# AK9753_Human_Movement_Sensor.net
KiCad netlist of a schematic drawn in EAGLE
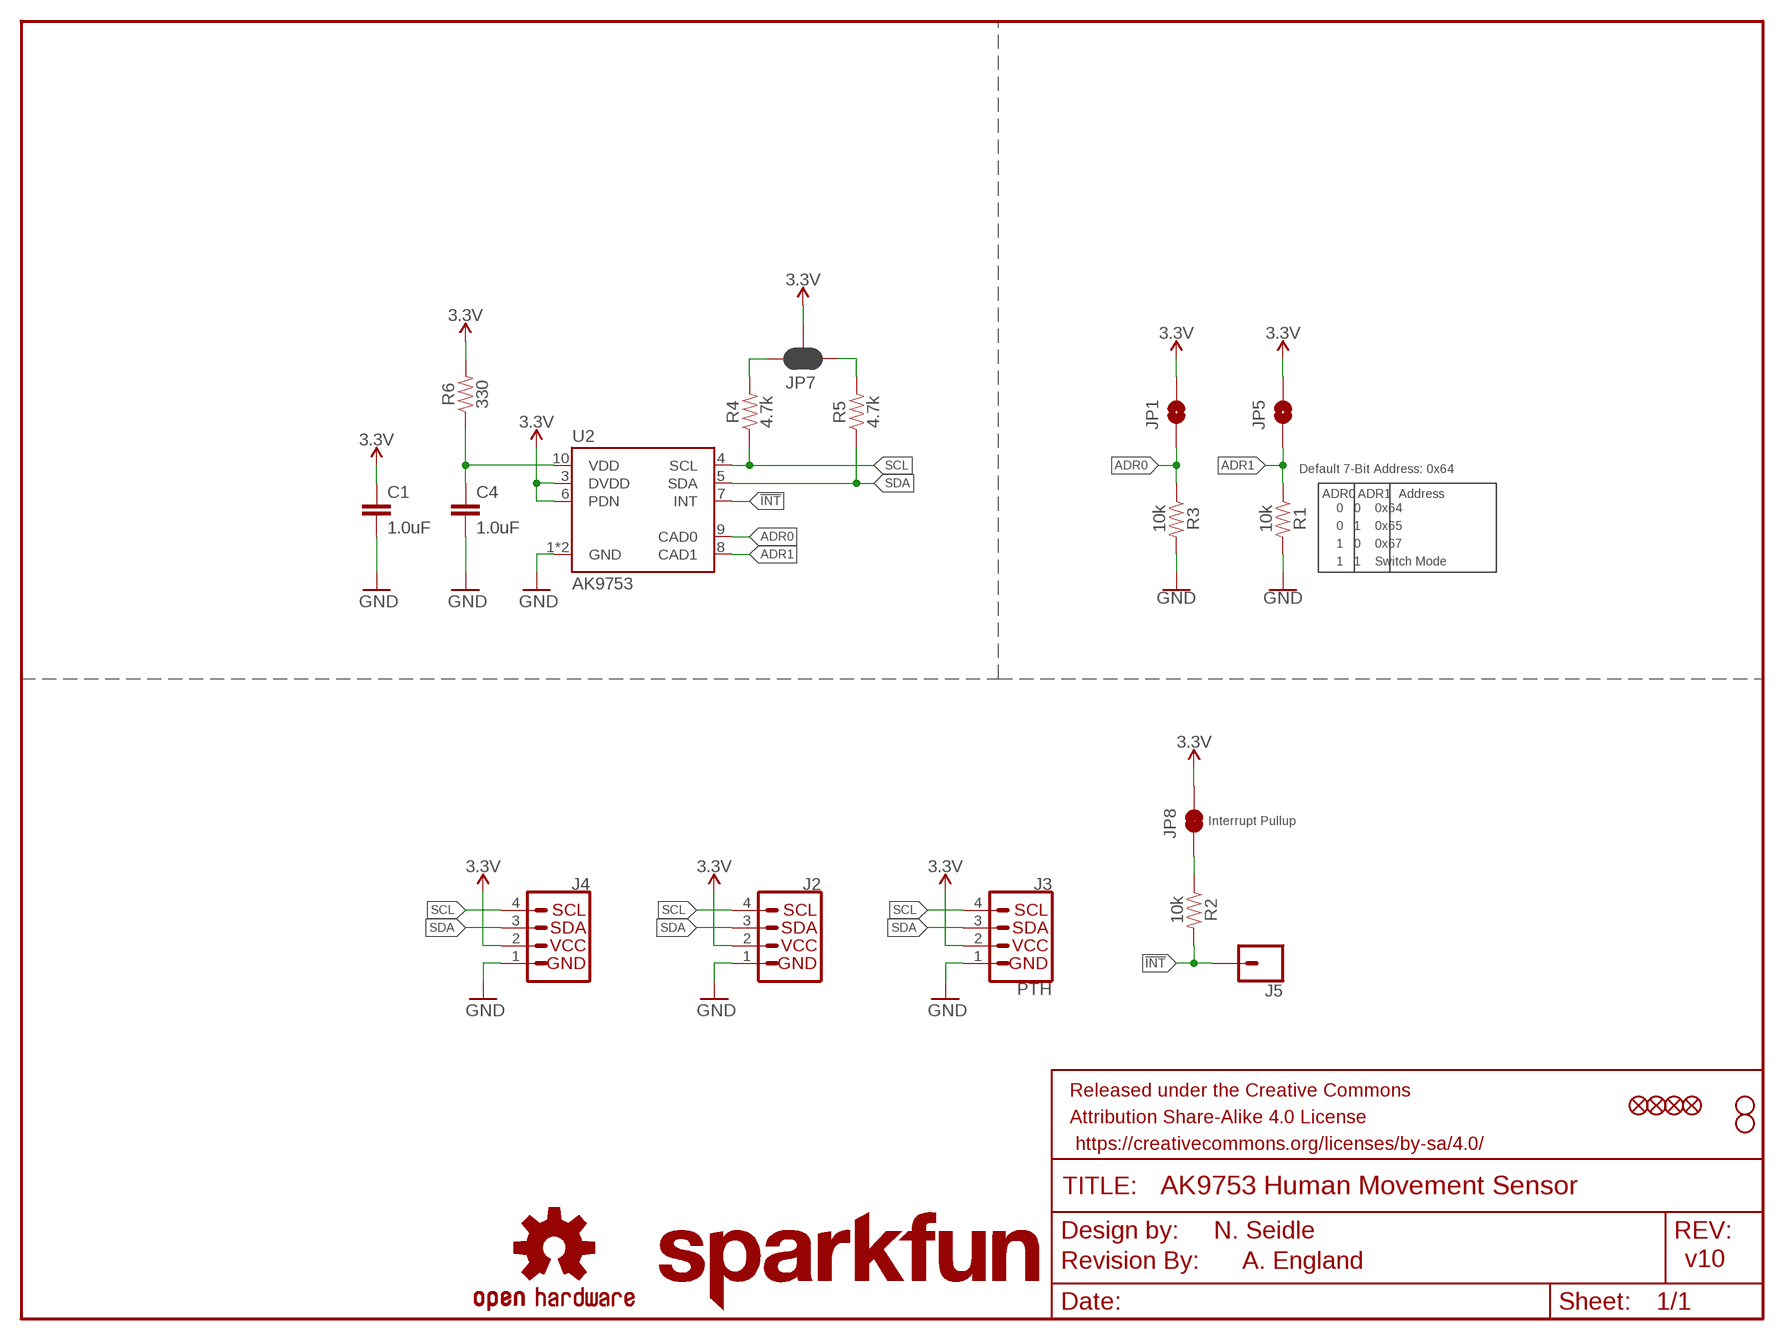
[diagram p0: schematic, sheet 1]

(export (version "E")
  (design (tool "Eeschema 10.0.6"))
  (components
    (comp (ref "C1")
      (value "1.0uF")
      (footprint "eagle-import:0603")
      (libsource (lib "eagle-import") (part "1.0UF-0603-16V-10%"))
    )
    (comp (ref "C4")
      (value "1.0uF")
      (footprint "eagle-import:0603")
      (libsource (lib "eagle-import") (part "1.0UF-0603-16V-10%"))
    )
    (comp (ref "FRAME1")
      (value "FRAME-LETTER")
      (footprint "eagle-import:CREATIVE_COMMONS")
      (libsource (lib "eagle-import") (part "FRAME-LETTER"))
    )
    (comp (ref "J2")
      (value "QWIIC_CONNECTORJS-1MM")
      (footprint "eagle-import:1X04_1MM_RA")
      (libsource (lib "eagle-import") (part "QWIIC_CONNECTORJS-1MM"))
    )
    (comp (ref "J3")
      (value "PTH")
      (footprint "eagle-import:1X04_NO_SILK")
      (libsource (lib "eagle-import") (part "I2C_STANDARD_NO_SILK"))
    )
    (comp (ref "J4")
      (value "QWIIC_CONNECTORJS-1MM")
      (footprint "eagle-import:1X04_1MM_RA")
      (libsource (lib "eagle-import") (part "QWIIC_CONNECTORJS-1MM"))
    )
    (comp (ref "J5")
      (value "CONN_01PTH_NO_SILK_YES_STOP")
      (footprint "eagle-import:1X01_NO_SILK")
      (libsource (lib "eagle-import") (part "CONN_01PTH_NO_SILK_YES_STOP"))
    )
    (comp (ref "JP1")
      (value "JUMPER-SMT_2_NO_SILK")
      (footprint "eagle-import:SMT-JUMPER_2_NO_SILK")
      (libsource (lib "eagle-import") (part "JUMPER-SMT_2_NO_SILK"))
    )
    (comp (ref "JP2")
      (value "FIDUCIALUFIDUCIAL")
      (footprint "eagle-import:MICRO-FIDUCIAL")
      (libsource (lib "eagle-import") (part "FIDUCIALUFIDUCIAL"))
    )
    (comp (ref "JP3")
      (value "STAND-OFF")
      (footprint "eagle-import:STAND-OFF")
      (libsource (lib "eagle-import") (part "STAND-OFF"))
    )
    (comp (ref "JP4")
      (value "STAND-OFF")
      (footprint "eagle-import:STAND-OFF")
      (libsource (lib "eagle-import") (part "STAND-OFF"))
    )
    (comp (ref "JP5")
      (value "JUMPER-SMT_2_NO_SILK")
      (footprint "eagle-import:SMT-JUMPER_2_NO_SILK")
      (libsource (lib "eagle-import") (part "JUMPER-SMT_2_NO_SILK"))
    )
    (comp (ref "JP6")
      (value "FIDUCIALUFIDUCIAL")
      (footprint "eagle-import:MICRO-FIDUCIAL")
      (libsource (lib "eagle-import") (part "FIDUCIALUFIDUCIAL"))
    )
    (comp (ref "JP7")
      (value "JUMPER-SMT_3_2-NC_PASTE_SILK")
      (footprint "eagle-import:SMT-JUMPER_3_2-NC_PASTE_SILK")
      (libsource (lib "eagle-import") (part "JUMPER-SMT_3_2-NC_PASTE_SILK"))
    )
    (comp (ref "JP8")
      (value "JUMPER-SMT_2_NC_TRACE_SILK")
      (footprint "eagle-import:SMT-JUMPER_2_NC_TRACE_SILK")
      (libsource (lib "eagle-import") (part "JUMPER-SMT_2_NC_TRACE_SILK"))
    )
    (comp (ref "JP9")
      (value "FIDUCIALUFIDUCIAL")
      (footprint "eagle-import:MICRO-FIDUCIAL")
      (libsource (lib "eagle-import") (part "FIDUCIALUFIDUCIAL"))
    )
    (comp (ref "JP10")
      (value "FIDUCIALUFIDUCIAL")
      (footprint "eagle-import:MICRO-FIDUCIAL")
      (libsource (lib "eagle-import") (part "FIDUCIALUFIDUCIAL"))
    )
    (comp (ref "LOGO1")
      (value "OSHW-LOGOMINI")
      (footprint "eagle-import:OSHW-LOGO-MINI")
      (libsource (lib "eagle-import") (part "OSHW-LOGOMINI"))
    )
    (comp (ref "LOGO2")
      (value "SFE_LOGO_NAME.1_INCH")
      (footprint "eagle-import:SFE_LOGO_NAME_.1")
      (libsource (lib "eagle-import") (part "SFE_LOGO_NAME.1_INCH"))
    )
    (comp (ref "LOGO3")
      (value "REVISION")
      (footprint "eagle-import:REVISION")
      (libsource (lib "eagle-import") (part "REVISION"))
    )
    (comp (ref "R1")
      (value "10k")
      (footprint "eagle-import:0603")
      (libsource (lib "eagle-import") (part "10KOHM-0603-1/10W-1%"))
    )
    (comp (ref "R2")
      (value "10k")
      (footprint "eagle-import:0603")
      (libsource (lib "eagle-import") (part "10KOHM-0603-1/10W-1%"))
    )
    (comp (ref "R3")
      (value "10k")
      (footprint "eagle-import:0603")
      (libsource (lib "eagle-import") (part "10KOHM-0603-1/10W-1%"))
    )
    (comp (ref "R4")
      (value "4.7k")
      (footprint "eagle-import:0603")
      (libsource (lib "eagle-import") (part "4.7KOHM-0603-1/10W-1%"))
    )
    (comp (ref "R5")
      (value "4.7k")
      (footprint "eagle-import:0603")
      (libsource (lib "eagle-import") (part "4.7KOHM-0603-1/10W-1%"))
    )
    (comp (ref "R6")
      (value "330")
      (footprint "eagle-import:0603")
      (libsource (lib "eagle-import") (part "330OHM-0603-1/10W-1%"))
    )
    (comp (ref "U2")
      (value "AK9753")
      (footprint "eagle-import:SON10")
      (libsource (lib "eagle-import") (part "AK9750{dblquote}"))
    )
  )
  (nets
    (net (code "1") (name "/~{INT}") (class "Default")
      (node (ref "J5") (pin "1") (pinfunction "1_1") (pintype "passive"))
      (node (ref "R2") (pin "2") (pinfunction "2_2") (pintype "passive"))
      (node (ref "U2") (pin "7") (pinfunction "INT_7") (pintype "bidirectional"))
    )
    (net (code "2") (name "3.3V") (class "Default")
      (node (ref "C1") (pin "1") (pinfunction "1_1") (pintype "passive"))
      (node (ref "J2") (pin "2") (pinfunction "2_2") (pintype "power_in"))
      (node (ref "J3") (pin "2") (pinfunction "2_2") (pintype "power_in"))
      (node (ref "J4") (pin "2") (pinfunction "2_2") (pintype "power_in"))
      (node (ref "JP1") (pin "2") (pinfunction "2_2") (pintype "passive"))
      (node (ref "JP5") (pin "2") (pinfunction "2_2") (pintype "passive"))
      (node (ref "JP7") (pin "2") (pinfunction "2_2") (pintype "passive"))
      (node (ref "JP8") (pin "2") (pinfunction "2_2") (pintype "passive"))
      (node (ref "R6") (pin "2") (pinfunction "2_2") (pintype "passive"))
      (node (ref "U2") (pin "3") (pinfunction "DVDD_3") (pintype "bidirectional"))
      (node (ref "U2") (pin "6") (pinfunction "PDN_6") (pintype "bidirectional"))
    )
    (net (code "3") (name "ADR0") (class "Default")
      (node (ref "JP1") (pin "1") (pinfunction "1_1") (pintype "passive"))
      (node (ref "R3") (pin "1") (pinfunction "1_1") (pintype "passive"))
      (node (ref "U2") (pin "9") (pinfunction "CAD0_9") (pintype "bidirectional"))
    )
    (net (code "4") (name "ADR1") (class "Default")
      (node (ref "JP5") (pin "1") (pinfunction "1_1") (pintype "passive"))
      (node (ref "R1") (pin "1") (pinfunction "1_1") (pintype "passive"))
      (node (ref "U2") (pin "8") (pinfunction "CAD1_8") (pintype "bidirectional"))
    )
    (net (code "5") (name "GND") (class "Default")
      (node (ref "C1") (pin "2") (pinfunction "2_2") (pintype "passive"))
      (node (ref "C4") (pin "2") (pinfunction "2_2") (pintype "passive"))
      (node (ref "J2") (pin "1") (pinfunction "1_1") (pintype "power_in"))
      (node (ref "J3") (pin "1") (pinfunction "1_1") (pintype "power_in"))
      (node (ref "J4") (pin "1") (pinfunction "1_1") (pintype "power_in"))
      (node (ref "R1") (pin "2") (pinfunction "2_2") (pintype "passive"))
      (node (ref "R3") (pin "2") (pinfunction "2_2") (pintype "passive"))
      (node (ref "U2") (pin "1") (pinfunction "GND_1") (pintype "bidirectional"))
      (node (ref "U2") (pin "2") (pinfunction "GND_2") (pintype "bidirectional"))
    )
    (net (code "6") (name "Net-(JP7-Pad1)") (class "Default")
      (node (ref "JP7") (pin "1") (pinfunction "1_1") (pintype "passive"))
      (node (ref "R5") (pin "2") (pinfunction "2_2") (pintype "passive"))
    )
    (net (code "7") (name "Net-(JP7-Pad3)") (class "Default")
      (node (ref "JP7") (pin "3") (pinfunction "3_3") (pintype "passive"))
      (node (ref "R4") (pin "2") (pinfunction "2_2") (pintype "passive"))
    )
    (net (code "8") (name "Net-(JP8-Pad1)") (class "Default")
      (node (ref "JP8") (pin "1") (pinfunction "1_1") (pintype "passive"))
      (node (ref "R2") (pin "1") (pinfunction "1_1") (pintype "passive"))
    )
    (net (code "9") (name "Net-(U2-VDD)") (class "Default")
      (node (ref "C4") (pin "1") (pinfunction "1_1") (pintype "passive"))
      (node (ref "R6") (pin "1") (pinfunction "1_1") (pintype "passive"))
      (node (ref "U2") (pin "10") (pinfunction "VDD_10") (pintype "bidirectional"))
    )
    (net (code "10") (name "SCL") (class "Default")
      (node (ref "J2") (pin "4") (pinfunction "4_4") (pintype "passive"))
      (node (ref "J3") (pin "4") (pinfunction "4_4") (pintype "passive"))
      (node (ref "J4") (pin "4") (pinfunction "4_4") (pintype "passive"))
      (node (ref "R4") (pin "1") (pinfunction "1_1") (pintype "passive"))
      (node (ref "U2") (pin "4") (pinfunction "SCL_4") (pintype "bidirectional"))
    )
    (net (code "11") (name "SDA") (class "Default")
      (node (ref "J2") (pin "3") (pinfunction "3_3") (pintype "passive"))
      (node (ref "J3") (pin "3") (pinfunction "3_3") (pintype "passive"))
      (node (ref "J4") (pin "3") (pinfunction "3_3") (pintype "passive"))
      (node (ref "R5") (pin "1") (pinfunction "1_1") (pintype "passive"))
      (node (ref "U2") (pin "5") (pinfunction "SDA_5") (pintype "bidirectional"))
    )
  )
)
